# twin_coil_rev_3_20170625c.net
KiCad netlist of a schematic drawn in EAGLE
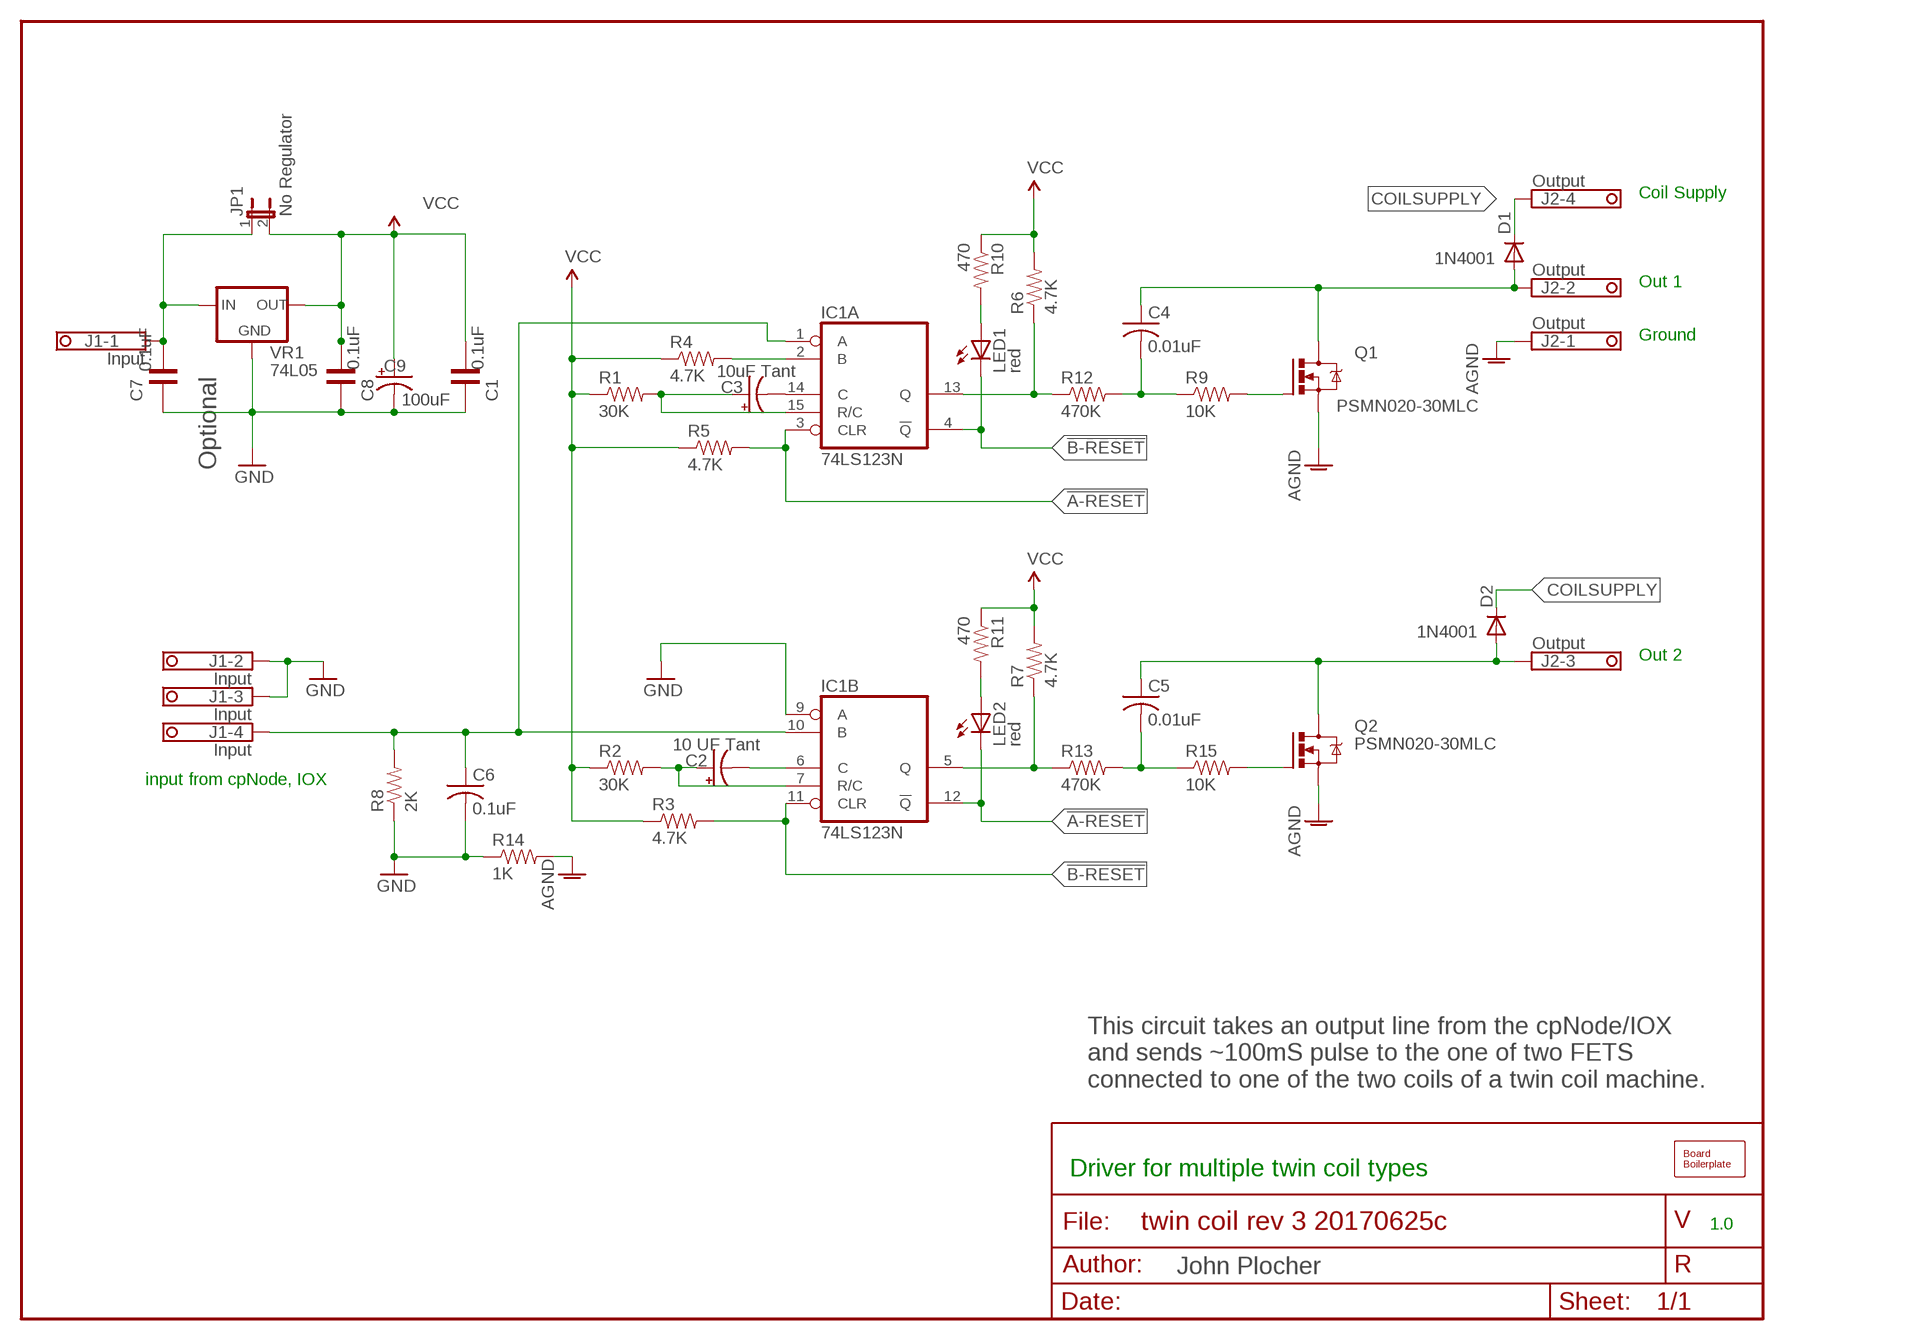
[diagram p0: schematic, sheet 1]

(export (version "E")
  (design (tool "Eeschema 10.0.6"))
  (components
    (comp (ref "BOARD1")
      (value "BOARD69X70")
      (footprint "eagle-import:BOARD-DINRAIL-2.7INX7CM")
      (libsource (lib "eagle-import") (part "BOARD69X70"))
    )
    (comp (ref "C1")
      (value "0.1uF")
      (footprint "eagle-import:CAP-PTH-SMALL")
      (libsource (lib "eagle-import") (part "CPTH"))
    )
    (comp (ref "C2")
      (value "10 UF Tant")
      (footprint "eagle-import:E5-4")
      (libsource (lib "eagle-import") (part "CPOL-USE5-4"))
    )
    (comp (ref "C3")
      (value "10uF Tant")
      (footprint "eagle-import:E5-4")
      (libsource (lib "eagle-import") (part "CPOL-USE5-4"))
    )
    (comp (ref "C4")
      (value "0.01uF")
      (footprint "eagle-import:C025-030X050")
      (libsource (lib "eagle-import") (part "C-US025-030X050"))
    )
    (comp (ref "C5")
      (value "0.01uF")
      (footprint "eagle-import:C025-030X050")
      (libsource (lib "eagle-import") (part "C-US025-030X050"))
    )
    (comp (ref "C6")
      (value "0.1uF")
      (footprint "eagle-import:C025-030X050")
      (libsource (lib "eagle-import") (part "C-US025-030X050"))
    )
    (comp (ref "C7")
      (value "0.1uF")
      (footprint "eagle-import:CAP-PTH-SMALL")
      (libsource (lib "eagle-import") (part "CPTH"))
    )
    (comp (ref "C8")
      (value "0.1uF")
      (footprint "eagle-import:CAP-PTH-SMALL")
      (libsource (lib "eagle-import") (part "CPTH"))
    )
    (comp (ref "C9")
      (value "100uF")
      (footprint "eagle-import:E3,5-10")
      (libsource (lib "eagle-import") (part "CPOL-USE3.5-10"))
    )
    (comp (ref "D1")
      (value "1N4001")
      (footprint "eagle-import:DIODE-1N4001")
      (libsource (lib "eagle-import") (part "DIODEPTH"))
    )
    (comp (ref "D2")
      (value "1N4001")
      (footprint "eagle-import:DIODE-1N4001")
      (libsource (lib "eagle-import") (part "DIODEPTH"))
    )
    (comp (ref "IC1")
      (value "74LS123N")
      (footprint "eagle-import:DIL16")
      (libsource (lib "eagle-import") (part "74123NLS"))
    )
    (comp (ref "J1")
      (value "Input")
      (footprint "eagle-import:1751264")
      (fields (field (name "MPN") "1751264"))
      (libsource (lib "eagle-import") (part "1751264"))
    )
    (comp (ref "J2")
      (value "Output")
      (footprint "eagle-import:1751264")
      (fields (field (name "MPN") "1751264"))
      (libsource (lib "eagle-import") (part "1751264"))
    )
    (comp (ref "JP1")
      (value "No Regulator")
      (footprint "eagle-import:1X02_LOCK")
      (libsource (lib "eagle-import") (part "JUMPER-2PTH_LOCK"))
    )
    (comp (ref "LED1")
      (value "red")
      (footprint "eagle-import:LED3MM")
      (libsource (lib "eagle-import") (part "LED3MM"))
    )
    (comp (ref "LED2")
      (value "red")
      (footprint "eagle-import:LED3MM")
      (libsource (lib "eagle-import") (part "LED3MM"))
    )
    (comp (ref "Q1")
      (value "PSMN020-30MLC")
      (footprint "eagle-import:TO220BV")
      (libsource (lib "eagle-import") (part "STP5NA50"))
    )
    (comp (ref "Q2")
      (value "PSMN020-30MLC")
      (footprint "eagle-import:TO220BV")
      (libsource (lib "eagle-import") (part "STP5NA50"))
    )
    (comp (ref "R1")
      (value "30K")
      (footprint "eagle-import:AXIAL-0.4")
      (libsource (lib "eagle-import") (part "RESISTORPTH-1/4W"))
    )
    (comp (ref "R2")
      (value "30K")
      (footprint "eagle-import:AXIAL-0.4")
      (libsource (lib "eagle-import") (part "RESISTORPTH-1/4W"))
    )
    (comp (ref "R3")
      (value "4.7K")
      (footprint "eagle-import:AXIAL-0.4")
      (libsource (lib "eagle-import") (part "RESISTORPTH-1/4W"))
    )
    (comp (ref "R4")
      (value "4.7K")
      (footprint "eagle-import:AXIAL-0.4")
      (libsource (lib "eagle-import") (part "RESISTORPTH-1/4W"))
    )
    (comp (ref "R5")
      (value "4.7K")
      (footprint "eagle-import:AXIAL-0.4")
      (libsource (lib "eagle-import") (part "RESISTORPTH-1/4W"))
    )
    (comp (ref "R6")
      (value "4.7K")
      (footprint "eagle-import:AXIAL-0.4")
      (libsource (lib "eagle-import") (part "RESISTORPTH-1/4W"))
    )
    (comp (ref "R7")
      (value "4.7K")
      (footprint "eagle-import:AXIAL-0.4")
      (libsource (lib "eagle-import") (part "RESISTORPTH-1/4W"))
    )
    (comp (ref "R8")
      (value "2K")
      (footprint "eagle-import:AXIAL-0.4")
      (libsource (lib "eagle-import") (part "RESISTORPTH-1/4W"))
    )
    (comp (ref "R9")
      (value "10K")
      (footprint "eagle-import:AXIAL-0.4")
      (libsource (lib "eagle-import") (part "RESISTORPTH-1/4W"))
    )
    (comp (ref "R10")
      (value "470")
      (footprint "eagle-import:AXIAL-0.4")
      (libsource (lib "eagle-import") (part "RESISTORPTH-1/4W"))
    )
    (comp (ref "R11")
      (value "470")
      (footprint "eagle-import:AXIAL-0.4")
      (libsource (lib "eagle-import") (part "RESISTORPTH-1/4W"))
    )
    (comp (ref "R12")
      (value "470K")
      (footprint "eagle-import:AXIAL-0.4")
      (libsource (lib "eagle-import") (part "RESISTORPTH-1/4W"))
    )
    (comp (ref "R13")
      (value "470K")
      (footprint "eagle-import:AXIAL-0.4")
      (libsource (lib "eagle-import") (part "RESISTORPTH-1/4W"))
    )
    (comp (ref "R14")
      (value "1K")
      (footprint "eagle-import:AXIAL-0.4")
      (libsource (lib "eagle-import") (part "RESISTORPTH-1/4W"))
    )
    (comp (ref "R15")
      (value "10K")
      (footprint "eagle-import:AXIAL-0.4")
      (libsource (lib "eagle-import") (part "RESISTORPTH-1/4W"))
    )
    (comp (ref "VR1")
      (value "74L05")
      (footprint "eagle-import:TO-92")
      (libsource (lib "eagle-import") (part "V_REG_78XXTO-92_UNTESTED"))
    )
  )
  (nets
    (net (code "1") (name "/~{A-RESET}") (class "Default")
      (node (ref "IC1") (pin "12") (pinfunction "~{Q}_12") (pintype "output"))
      (node (ref "IC1") (pin "3") (pinfunction "CLR_3") (pintype "input"))
      (node (ref "LED2") (pin "K") (pinfunction "C_K") (pintype "passive"))
      (node (ref "R5") (pin "P$2") (pinfunction "2_P$2") (pintype "passive"))
    )
    (net (code "2") (name "/~{B-RESET}") (class "Default")
      (node (ref "IC1") (pin "11") (pinfunction "CLR_11") (pintype "input"))
      (node (ref "IC1") (pin "4") (pinfunction "~{Q}_4") (pintype "output"))
      (node (ref "LED1") (pin "K") (pinfunction "C_K") (pintype "passive"))
      (node (ref "R3") (pin "P$2") (pinfunction "2_P$2") (pintype "passive"))
    )
    (net (code "3") (name "AGND") (class "Default")
      (node (ref "J2") (pin "1") (pinfunction "K_1") (pintype "passive"))
      (node (ref "Q1") (pin "S") (pinfunction "S_S") (pintype "passive"))
      (node (ref "Q2") (pin "S") (pinfunction "S_S") (pintype "passive"))
      (node (ref "R14") (pin "P$2") (pinfunction "2_P$2") (pintype "passive"))
    )
    (net (code "4") (name "COILSUPPLY") (class "Default")
      (node (ref "D1") (pin "C") (pinfunction "C_C") (pintype "passive"))
      (node (ref "D2") (pin "C") (pinfunction "C_C") (pintype "passive"))
      (node (ref "J2") (pin "4") (pinfunction "K_4") (pintype "passive"))
    )
    (net (code "5") (name "GND") (class "Default")
      (node (ref "C1") (pin "1") (pinfunction "1_1") (pintype "passive"))
      (node (ref "C6") (pin "2") (pinfunction "2_2") (pintype "passive"))
      (node (ref "C7") (pin "1") (pinfunction "1_1") (pintype "passive"))
      (node (ref "C8") (pin "1") (pinfunction "1_1") (pintype "passive"))
      (node (ref "C9") (pin "-") (pinfunction "-_-") (pintype "passive"))
      (node (ref "IC1") (pin "9") (pinfunction "A_9") (pintype "input"))
      (node (ref "J1") (pin "2") (pinfunction "K_2") (pintype "passive"))
      (node (ref "J1") (pin "3") (pinfunction "K_3") (pintype "passive"))
      (node (ref "R14") (pin "P$1") (pinfunction "1_P$1") (pintype "passive"))
      (node (ref "R8") (pin "P$1") (pinfunction "1_P$1") (pintype "passive"))
      (node (ref "VR1") (pin "2") (pinfunction "GND_2") (pintype "input"))
    )
    (net (code "6") (name "Net-(IC1A-A)") (class "Default")
      (node (ref "C6") (pin "1") (pinfunction "1_1") (pintype "passive"))
      (node (ref "IC1") (pin "1") (pinfunction "A_1") (pintype "input"))
      (node (ref "IC1") (pin "10") (pinfunction "B_10") (pintype "input"))
      (node (ref "J1") (pin "4") (pinfunction "K_4") (pintype "passive"))
      (node (ref "R8") (pin "P$2") (pinfunction "2_P$2") (pintype "passive"))
    )
    (net (code "7") (name "Net-(IC1A-B)") (class "Default")
      (node (ref "IC1") (pin "2") (pinfunction "B_2") (pintype "input"))
      (node (ref "R4") (pin "P$2") (pinfunction "2_P$2") (pintype "passive"))
    )
    (net (code "8") (name "Net-(IC1A-C)") (class "Default")
      (node (ref "C3") (pin "-") (pinfunction "-_-") (pintype "passive"))
      (node (ref "IC1") (pin "14") (pinfunction "C_14") (pintype "input"))
    )
    (net (code "9") (name "Net-(IC1A-Q)") (class "Default")
      (node (ref "IC1") (pin "13") (pinfunction "Q_13") (pintype "output"))
      (node (ref "R12") (pin "P$1") (pinfunction "1_P$1") (pintype "passive"))
      (node (ref "R6") (pin "P$1") (pinfunction "1_P$1") (pintype "passive"))
    )
    (net (code "10") (name "Net-(IC1A-R{slash}C)") (class "Default")
      (node (ref "C3") (pin "+") (pinfunction "+_+") (pintype "passive"))
      (node (ref "IC1") (pin "15") (pinfunction "R/C_15") (pintype "input"))
      (node (ref "R1") (pin "P$2") (pinfunction "2_P$2") (pintype "passive"))
    )
    (net (code "11") (name "Net-(IC1B-C)") (class "Default")
      (node (ref "C2") (pin "-") (pinfunction "-_-") (pintype "passive"))
      (node (ref "IC1") (pin "6") (pinfunction "C_6") (pintype "input"))
    )
    (net (code "12") (name "Net-(IC1B-Q)") (class "Default")
      (node (ref "IC1") (pin "5") (pinfunction "Q_5") (pintype "output"))
      (node (ref "R13") (pin "P$1") (pinfunction "1_P$1") (pintype "passive"))
      (node (ref "R7") (pin "P$1") (pinfunction "1_P$1") (pintype "passive"))
    )
    (net (code "13") (name "Net-(IC1B-R{slash}C)") (class "Default")
      (node (ref "C2") (pin "+") (pinfunction "+_+") (pintype "passive"))
      (node (ref "IC1") (pin "7") (pinfunction "R/C_7") (pintype "input"))
      (node (ref "R2") (pin "P$2") (pinfunction "2_P$2") (pintype "passive"))
    )
    (net (code "14") (name "Net-(J1A-K)") (class "Default")
      (node (ref "C7") (pin "2") (pinfunction "2_2") (pintype "passive"))
      (node (ref "J1") (pin "1") (pinfunction "K_1") (pintype "passive"))
      (node (ref "JP1") (pin "1") (pinfunction "1_1") (pintype "passive"))
      (node (ref "VR1") (pin "3") (pinfunction "IN_3") (pintype "input"))
    )
    (net (code "15") (name "Net-(J2B-K)") (class "Default")
      (node (ref "C4") (pin "1") (pinfunction "1_1") (pintype "passive"))
      (node (ref "D1") (pin "A") (pinfunction "A_A") (pintype "passive"))
      (node (ref "J2") (pin "2") (pinfunction "K_2") (pintype "passive"))
      (node (ref "Q1") (pin "D") (pinfunction "D_D") (pintype "passive"))
    )
    (net (code "16") (name "Net-(J2C-K)") (class "Default")
      (node (ref "C5") (pin "1") (pinfunction "1_1") (pintype "passive"))
      (node (ref "D2") (pin "A") (pinfunction "A_A") (pintype "passive"))
      (node (ref "J2") (pin "3") (pinfunction "K_3") (pintype "passive"))
      (node (ref "Q2") (pin "D") (pinfunction "D_D") (pintype "passive"))
    )
    (net (code "17") (name "Net-(R9-2)") (class "Default")
      (node (ref "Q1") (pin "G") (pinfunction "G_G") (pintype "passive"))
      (node (ref "R9") (pin "P$2") (pinfunction "2_P$2") (pintype "passive"))
    )
    (net (code "18") (name "Net-(R10-2)") (class "Default")
      (node (ref "LED1") (pin "A") (pinfunction "A_A") (pintype "passive"))
      (node (ref "R10") (pin "P$2") (pinfunction "2_P$2") (pintype "passive"))
    )
    (net (code "19") (name "Net-(R11-2)") (class "Default")
      (node (ref "LED2") (pin "A") (pinfunction "A_A") (pintype "passive"))
      (node (ref "R11") (pin "P$2") (pinfunction "2_P$2") (pintype "passive"))
    )
    (net (code "20") (name "Net-(R12-2)") (class "Default")
      (node (ref "C4") (pin "2") (pinfunction "2_2") (pintype "passive"))
      (node (ref "R12") (pin "P$2") (pinfunction "2_P$2") (pintype "passive"))
      (node (ref "R9") (pin "P$1") (pinfunction "1_P$1") (pintype "passive"))
    )
    (net (code "21") (name "Net-(R13-2)") (class "Default")
      (node (ref "C5") (pin "2") (pinfunction "2_2") (pintype "passive"))
      (node (ref "R13") (pin "P$2") (pinfunction "2_P$2") (pintype "passive"))
      (node (ref "R15") (pin "P$1") (pinfunction "1_P$1") (pintype "passive"))
    )
    (net (code "22") (name "Net-(R15-2)") (class "Default")
      (node (ref "Q2") (pin "G") (pinfunction "G_G") (pintype "passive"))
      (node (ref "R15") (pin "P$2") (pinfunction "2_P$2") (pintype "passive"))
    )
    (net (code "23") (name "VCC") (class "Default")
      (node (ref "C1") (pin "2") (pinfunction "2_2") (pintype "passive"))
      (node (ref "C8") (pin "2") (pinfunction "2_2") (pintype "passive"))
      (node (ref "C9") (pin "+") (pinfunction "+_+") (pintype "passive"))
      (node (ref "JP1") (pin "2") (pinfunction "2_2") (pintype "passive"))
      (node (ref "R1") (pin "P$1") (pinfunction "1_P$1") (pintype "passive"))
      (node (ref "R10") (pin "P$1") (pinfunction "1_P$1") (pintype "passive"))
      (node (ref "R11") (pin "P$1") (pinfunction "1_P$1") (pintype "passive"))
      (node (ref "R2") (pin "P$1") (pinfunction "1_P$1") (pintype "passive"))
      (node (ref "R3") (pin "P$1") (pinfunction "1_P$1") (pintype "passive"))
      (node (ref "R4") (pin "P$1") (pinfunction "1_P$1") (pintype "passive"))
      (node (ref "R5") (pin "P$1") (pinfunction "1_P$1") (pintype "passive"))
      (node (ref "R6") (pin "P$2") (pinfunction "2_P$2") (pintype "passive"))
      (node (ref "R7") (pin "P$2") (pinfunction "2_P$2") (pintype "passive"))
      (node (ref "VR1") (pin "1") (pinfunction "OUT_1") (pintype "passive"))
    )
  )
)
